# poi.net
KiCad netlist of a schematic drawn in EAGLE
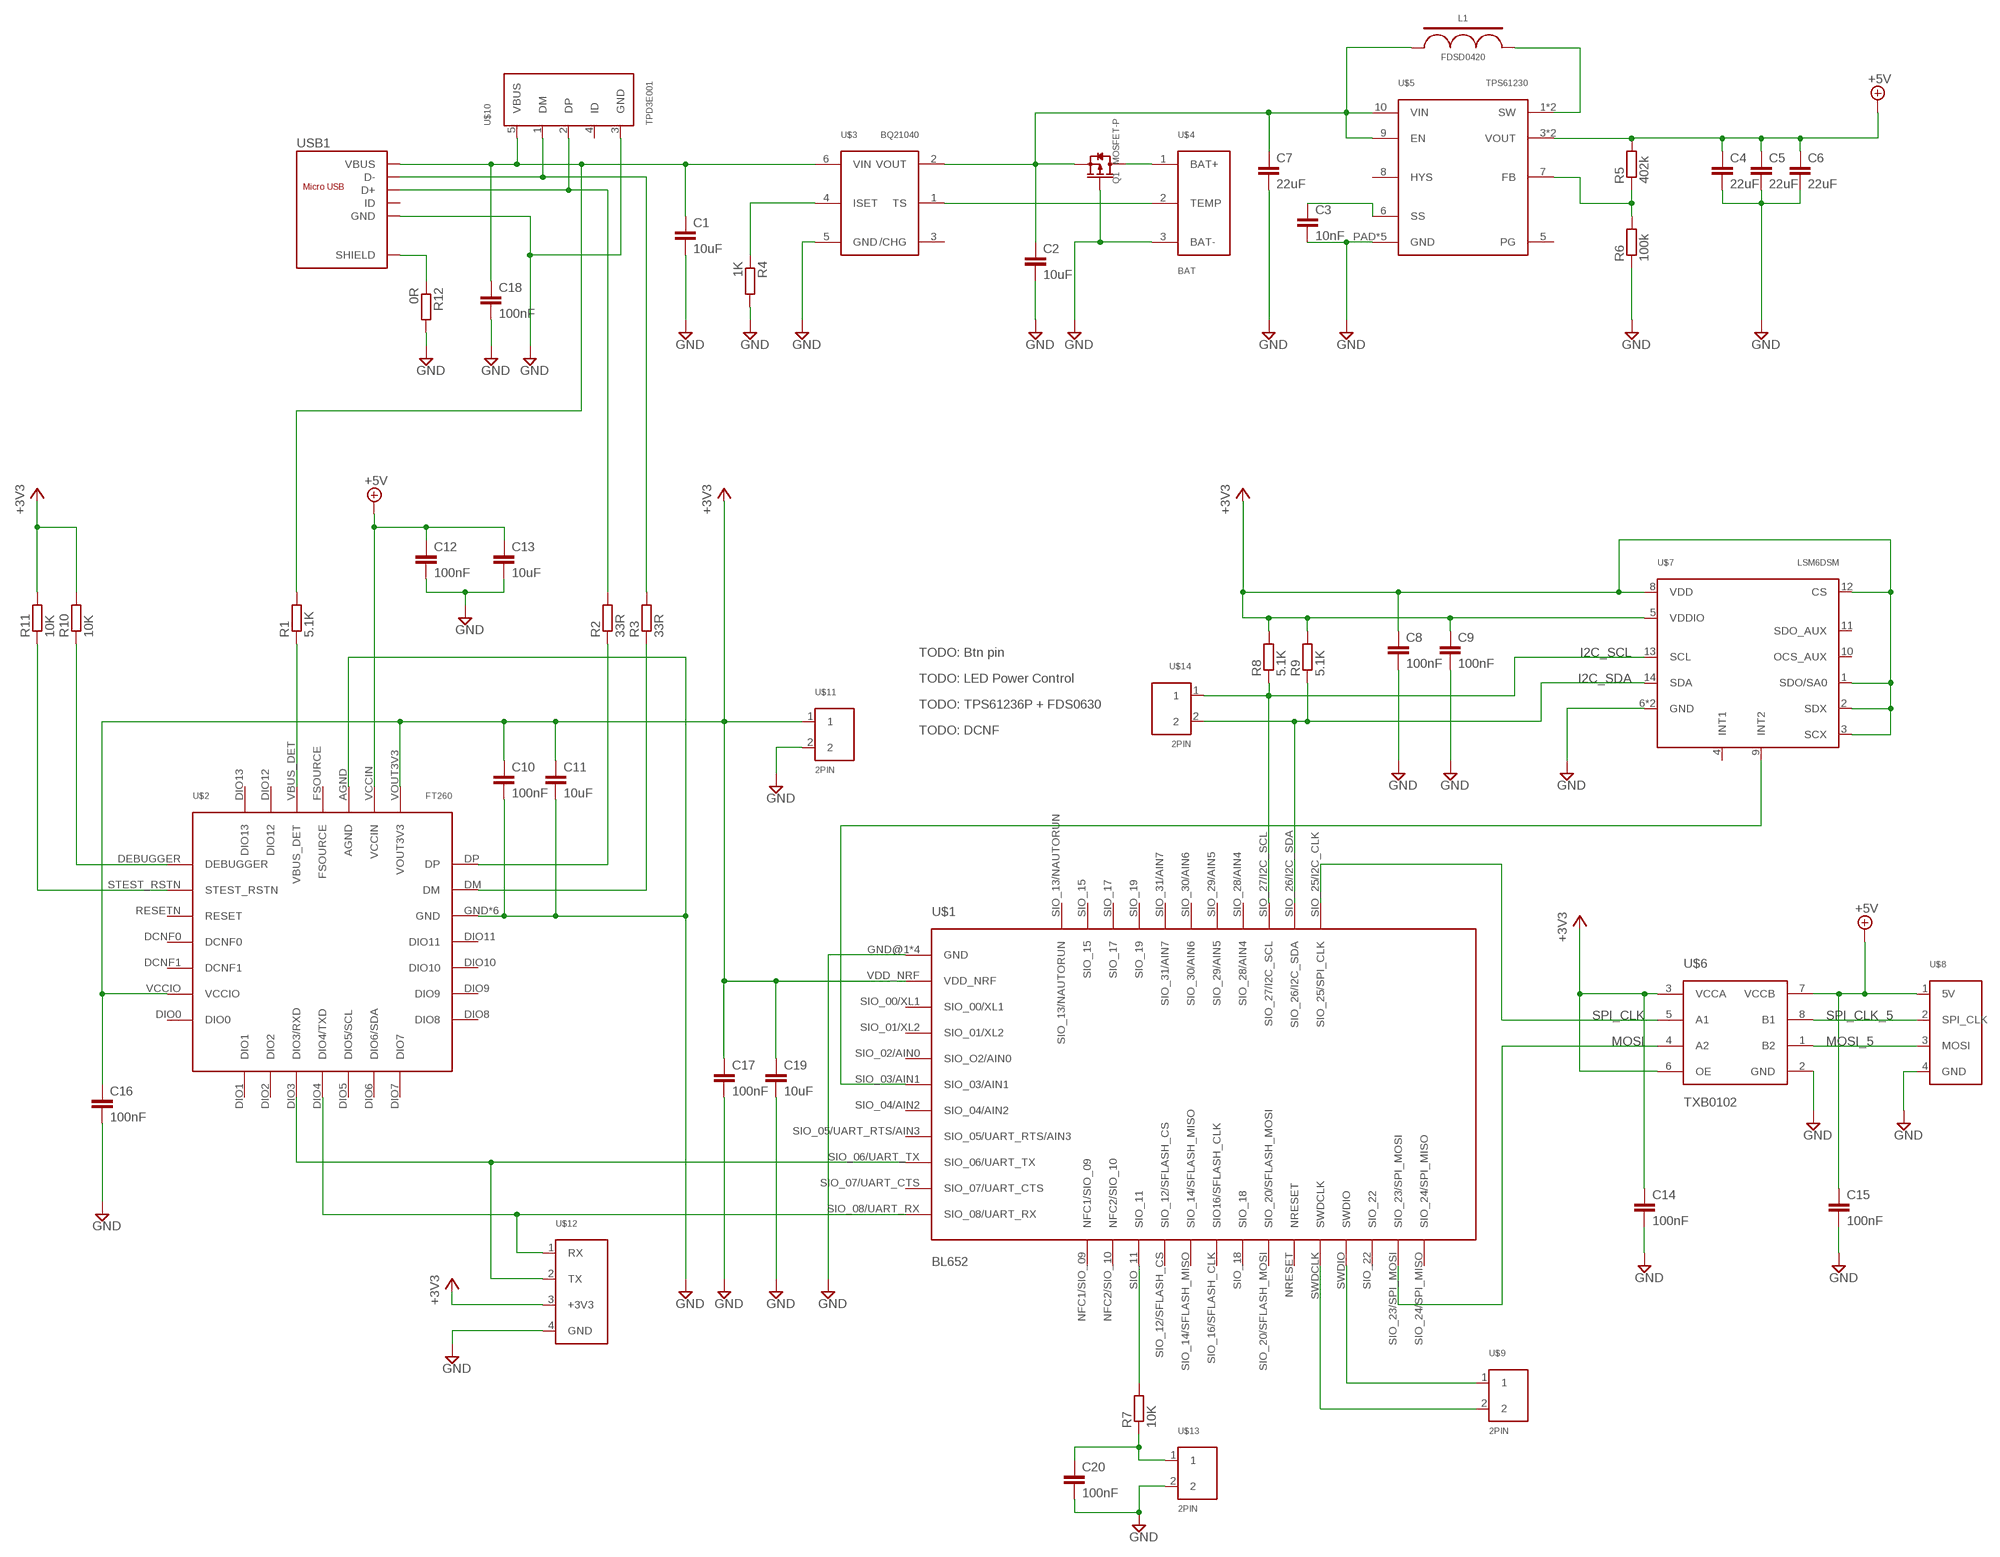
[diagram p0: schematic, sheet 1]

(export (version "E")
  (design (tool "Eeschema 10.0.6"))
  (components
    (comp (ref "C1")
      (value "10uF")
      (footprint "eagle-import:C0603")
      (libsource (lib "eagle-import") (part "C-EUC0603"))
    )
    (comp (ref "C2")
      (value "10uF")
      (footprint "eagle-import:C0603")
      (libsource (lib "eagle-import") (part "C-EUC0603"))
    )
    (comp (ref "C3")
      (value "10nF")
      (footprint "eagle-import:C0603")
      (libsource (lib "eagle-import") (part "C-EUC0603"))
    )
    (comp (ref "C4")
      (value "22uF")
      (footprint "eagle-import:C0603")
      (libsource (lib "eagle-import") (part "C-EUC0603"))
    )
    (comp (ref "C5")
      (value "22uF")
      (footprint "eagle-import:C0603")
      (libsource (lib "eagle-import") (part "C-EUC0603"))
    )
    (comp (ref "C6")
      (value "22uF")
      (footprint "eagle-import:C0603")
      (libsource (lib "eagle-import") (part "C-EUC0603"))
    )
    (comp (ref "C7")
      (value "22uF")
      (footprint "eagle-import:C0603")
      (libsource (lib "eagle-import") (part "C-EUC0603"))
    )
    (comp (ref "C8")
      (value "100nF")
      (footprint "eagle-import:C0603")
      (libsource (lib "eagle-import") (part "C-EUC0603"))
    )
    (comp (ref "C9")
      (value "100nF")
      (footprint "eagle-import:C0603")
      (libsource (lib "eagle-import") (part "C-EUC0603"))
    )
    (comp (ref "C10")
      (value "100nF")
      (footprint "eagle-import:C0603")
      (libsource (lib "eagle-import") (part "C-EUC0603"))
    )
    (comp (ref "C11")
      (value "10uF")
      (footprint "eagle-import:C0603")
      (libsource (lib "eagle-import") (part "C-EUC0603"))
    )
    (comp (ref "C12")
      (value "100nF")
      (footprint "eagle-import:C0603")
      (libsource (lib "eagle-import") (part "C-EUC0603"))
    )
    (comp (ref "C13")
      (value "10uF")
      (footprint "eagle-import:C0603")
      (libsource (lib "eagle-import") (part "C-EUC0603"))
    )
    (comp (ref "C14")
      (value "100nF")
      (footprint "eagle-import:C0603")
      (libsource (lib "eagle-import") (part "C-EUC0603"))
    )
    (comp (ref "C15")
      (value "100nF")
      (footprint "eagle-import:C0603")
      (libsource (lib "eagle-import") (part "C-EUC0603"))
    )
    (comp (ref "C16")
      (value "100nF")
      (footprint "eagle-import:C0603")
      (libsource (lib "eagle-import") (part "C-EUC0603"))
    )
    (comp (ref "C17")
      (value "100nF")
      (footprint "eagle-import:C0603")
      (libsource (lib "eagle-import") (part "C-EUC0603"))
    )
    (comp (ref "C18")
      (value "100nF")
      (footprint "eagle-import:C0603")
      (libsource (lib "eagle-import") (part "C-EUC0603"))
    )
    (comp (ref "C19")
      (value "10uF")
      (footprint "eagle-import:C0603")
      (libsource (lib "eagle-import") (part "C-EUC0603"))
    )
    (comp (ref "C20")
      (value "100nF")
      (footprint "eagle-import:C0603")
      (libsource (lib "eagle-import") (part "C-EUC0603"))
    )
    (comp (ref "L1")
      (value "FDSD0420")
      (footprint "eagle-import:FDSD0420")
      (libsource (lib "eagle-import") (part "FDSD0420"))
    )
    (comp (ref "Q1")
      (value "MOSFET-P")
      (footprint "eagle-import:SOT-23")
      (fields (field (name "MPN") "PMV65XPEA"))
      (libsource (lib "eagle-import") (part "MOSFET-P"))
    )
    (comp (ref "R1")
      (value "5.1K")
      (footprint "eagle-import:R0603")
      (libsource (lib "eagle-import") (part "R-EU_R0603"))
    )
    (comp (ref "R2")
      (value "33R")
      (footprint "eagle-import:R0603")
      (libsource (lib "eagle-import") (part "R-EU_R0603"))
    )
    (comp (ref "R3")
      (value "33R")
      (footprint "eagle-import:R0603")
      (libsource (lib "eagle-import") (part "R-EU_R0603"))
    )
    (comp (ref "R4")
      (value "1K")
      (footprint "eagle-import:R0603")
      (libsource (lib "eagle-import") (part "R-EU_R0603"))
    )
    (comp (ref "R5")
      (value "402k")
      (footprint "eagle-import:R0603")
      (libsource (lib "eagle-import") (part "R-EU_R0603"))
    )
    (comp (ref "R6")
      (value "100k")
      (footprint "eagle-import:R0603")
      (libsource (lib "eagle-import") (part "R-EU_R0603"))
    )
    (comp (ref "R7")
      (value "10K")
      (footprint "eagle-import:R0603")
      (libsource (lib "eagle-import") (part "R-EU_R0603"))
    )
    (comp (ref "R8")
      (value "5.1K")
      (footprint "eagle-import:R0603")
      (libsource (lib "eagle-import") (part "R-EU_R0603"))
    )
    (comp (ref "R9")
      (value "5.1K")
      (footprint "eagle-import:R0603")
      (libsource (lib "eagle-import") (part "R-EU_R0603"))
    )
    (comp (ref "R10")
      (value "10K")
      (footprint "eagle-import:R0603")
      (libsource (lib "eagle-import") (part "R-EU_R0603"))
    )
    (comp (ref "R11")
      (value "10K")
      (footprint "eagle-import:R0603")
      (libsource (lib "eagle-import") (part "R-EU_R0603"))
    )
    (comp (ref "R12")
      (value "0R")
      (footprint "eagle-import:R0603")
      (libsource (lib "eagle-import") (part "R-EU_R0603"))
    )
    (comp (ref "U$1")
      (value "BL652")
      (footprint "eagle-import:BL652")
      (fields (field (name "MF") "LAIRD") (field (name "MPN") "BL652-SA-01"))
      (libsource (lib "eagle-import") (part "BL652"))
    )
    (comp (ref "U$2")
      (value "FT260")
      (footprint "eagle-import:WQFN-28")
      (fields (field (name "MF") "FTDI") (field (name "MPN") "FT260Q-T"))
      (libsource (lib "eagle-import") (part "FT260"))
    )
    (comp (ref "U$3")
      (value "BQ21040")
      (footprint "eagle-import:SOT23-6")
      (fields (field (name "MF") "TEXAS INSTRUMENTS") (field (name "MPN") "BQ21040DBVT"))
      (libsource (lib "eagle-import") (part "BQ21040"))
    )
    (comp (ref "U$4")
      (value "BAT")
      (footprint "eagle-import:3PIN")
      (libsource (lib "eagle-import") (part "BAT"))
    )
    (comp (ref "U$5")
      (value "TPS61230")
      (footprint "eagle-import:VSON-10")
      (fields (field (name "MF") "TEXAS INSTRUMENTS") (field (name "MPN") " TPS61230DRCR TPS61230DRCR"))
      (libsource (lib "eagle-import") (part "TPS61230"))
    )
    (comp (ref "U$6")
      (value "TXB0102")
      (footprint "eagle-import:VSSOP-8")
      (fields (field (name "MF") "TEXAS INSTRUMENTS") (field (name "MPN") "TXB0102DCUR"))
      (libsource (lib "eagle-import") (part "TXB0102"))
    )
    (comp (ref "U$7")
      (value "LSM6DSM")
      (footprint "eagle-import:LGA-14L")
      (libsource (lib "eagle-import") (part "LSM6DSM"))
    )
    (comp (ref "U$8")
      (value "SPI-4PIN")
      (footprint "eagle-import:4PIN")
      (libsource (lib "eagle-import") (part "SPI-4PIN"))
    )
    (comp (ref "U$9")
      (value "2PIN")
      (footprint "eagle-import:2PIN")
      (libsource (lib "eagle-import") (part "2PIN"))
    )
    (comp (ref "U$10")
      (value "TPD3E001")
      (footprint "eagle-import:SOT-553")
      (libsource (lib "eagle-import") (part "TPD3E001"))
    )
    (comp (ref "U$11")
      (value "2PIN")
      (footprint "eagle-import:2PIN")
      (libsource (lib "eagle-import") (part "2PIN"))
    )
    (comp (ref "U$12")
      (value "UART-4PIN")
      (footprint "eagle-import:4PIN")
      (libsource (lib "eagle-import") (part "UART-4PIN"))
    )
    (comp (ref "U$13")
      (value "2PIN")
      (footprint "eagle-import:2PIN")
      (libsource (lib "eagle-import") (part "2PIN"))
    )
    (comp (ref "U$14")
      (value "2PIN")
      (footprint "eagle-import:2PIN")
      (libsource (lib "eagle-import") (part "2PIN"))
    )
    (comp (ref "USB1")
      (value "ZX62-B-5PA")
      (footprint "eagle-import:ZX62-B-5PA")
      (libsource (lib "eagle-import") (part "ZX62-B-5PA"))
    )
  )
  (nets
    (net (code "1") (name "+3V3") (class "Default")
      (node (ref "C10") (pin "1") (pinfunction "1_1") (pintype "passive"))
      (node (ref "C11") (pin "1") (pinfunction "1_1") (pintype "passive"))
      (node (ref "C14") (pin "1") (pinfunction "1_1") (pintype "passive"))
      (node (ref "C16") (pin "1") (pinfunction "1_1") (pintype "passive"))
      (node (ref "C17") (pin "1") (pinfunction "1_1") (pintype "passive"))
      (node (ref "C19") (pin "1") (pinfunction "1_1") (pintype "passive"))
      (node (ref "C8") (pin "1") (pinfunction "1_1") (pintype "passive"))
      (node (ref "C9") (pin "1") (pinfunction "1_1") (pintype "passive"))
      (node (ref "R10") (pin "2") (pinfunction "2_2") (pintype "passive"))
      (node (ref "R11") (pin "2") (pinfunction "2_2") (pintype "passive"))
      (node (ref "R8") (pin "2") (pinfunction "2_2") (pintype "passive"))
      (node (ref "R9") (pin "2") (pinfunction "2_2") (pintype "passive"))
      (node (ref "U$1") (pin "VDD_NRF") (pinfunction "VDD_NRF_VDD_NRF") (pintype "power_in"))
      (node (ref "U$11") (pin "1") (pinfunction "1_1") (pintype "bidirectional"))
      (node (ref "U$12") (pin "3") (pinfunction "+3V3_3") (pintype "power_in"))
      (node (ref "U$2") (pin "VCCIO") (pinfunction "VCCIO_VCCIO") (pintype "bidirectional"))
      (node (ref "U$2") (pin "VOUT3V3") (pinfunction "VOUT3V3_VOUT3V3") (pintype "bidirectional"))
      (node (ref "U$6") (pin "3") (pinfunction "VCCA_3") (pintype "power_in"))
      (node (ref "U$6") (pin "6") (pinfunction "OE_6") (pintype "input"))
      (node (ref "U$7") (pin "1") (pinfunction "SDO/SA0_1") (pintype "bidirectional"))
      (node (ref "U$7") (pin "12") (pinfunction "CS_12") (pintype "bidirectional"))
      (node (ref "U$7") (pin "2") (pinfunction "SDX_2") (pintype "bidirectional"))
      (node (ref "U$7") (pin "3") (pinfunction "SCX_3") (pintype "bidirectional"))
      (node (ref "U$7") (pin "5") (pinfunction "VDDIO_5") (pintype "bidirectional"))
      (node (ref "U$7") (pin "8") (pinfunction "VDD_8") (pintype "bidirectional"))
    )
    (net (code "2") (name "+5V") (class "Default")
      (node (ref "C12") (pin "1") (pinfunction "1_1") (pintype "passive"))
      (node (ref "C13") (pin "1") (pinfunction "1_1") (pintype "passive"))
      (node (ref "C15") (pin "1") (pinfunction "1_1") (pintype "passive"))
      (node (ref "C4") (pin "1") (pinfunction "1_1") (pintype "passive"))
      (node (ref "C5") (pin "1") (pinfunction "1_1") (pintype "passive"))
      (node (ref "C6") (pin "1") (pinfunction "1_1") (pintype "passive"))
      (node (ref "R5") (pin "2") (pinfunction "2_2") (pintype "passive"))
      (node (ref "U$2") (pin "VCCIN") (pinfunction "VCCIN_VCCIN") (pintype "bidirectional"))
      (node (ref "U$5") (pin "3") (pinfunction "VOUT_3") (pintype "power_in"))
      (node (ref "U$5") (pin "4") (pinfunction "VOUT_4") (pintype "power_in"))
      (node (ref "U$6") (pin "7") (pinfunction "VCCB_7") (pintype "power_in"))
      (node (ref "U$8") (pin "1") (pinfunction "5V_1") (pintype "power_in"))
    )
    (net (code "3") (name "/I2C_SCL") (class "Default")
      (node (ref "R8") (pin "1") (pinfunction "1_1") (pintype "passive"))
      (node (ref "U$1") (pin "SIO_27/I2C_SCL") (pinfunction "SIO_27/I2C_SCL_SIO_27/I2C_SCL") (pintype "bidirectional"))
      (node (ref "U$14") (pin "1") (pinfunction "1_1") (pintype "bidirectional"))
      (node (ref "U$7") (pin "13") (pinfunction "SCL_13") (pintype "bidirectional"))
    )
    (net (code "4") (name "/I2C_SDA") (class "Default")
      (node (ref "R9") (pin "1") (pinfunction "1_1") (pintype "passive"))
      (node (ref "U$1") (pin "SIO_26/I2C_SDA") (pinfunction "SIO_26/I2C_SDA_SIO_26/I2C_SDA") (pintype "bidirectional"))
      (node (ref "U$14") (pin "2") (pinfunction "2_2") (pintype "bidirectional"))
      (node (ref "U$7") (pin "14") (pinfunction "SDA_14") (pintype "bidirectional"))
    )
    (net (code "5") (name "/MOSI") (class "Default")
      (node (ref "U$1") (pin "SIO_23/SPI_MOSI") (pinfunction "SIO_23/SPI_MOSI_SIO_23/SPI_MOSI") (pintype "bidirectional"))
      (node (ref "U$6") (pin "4") (pinfunction "A2_4") (pintype "bidirectional"))
    )
    (net (code "6") (name "/MOSI_5") (class "Default")
      (node (ref "U$6") (pin "1") (pinfunction "B2_1") (pintype "bidirectional"))
      (node (ref "U$8") (pin "3") (pinfunction "MOSI_3") (pintype "output"))
    )
    (net (code "7") (name "/SPI_CLK") (class "Default")
      (node (ref "U$1") (pin "SIO_25/I2C_CLK") (pinfunction "SIO_25/SPI_CLK_SIO_25/I2C_CLK") (pintype "bidirectional"))
      (node (ref "U$6") (pin "5") (pinfunction "A1_5") (pintype "bidirectional"))
    )
    (net (code "8") (name "/SPI_CLK_5") (class "Default")
      (node (ref "U$6") (pin "8") (pinfunction "B1_8") (pintype "bidirectional"))
      (node (ref "U$8") (pin "2") (pinfunction "SPI_CLK_2") (pintype "input"))
    )
    (net (code "9") (name "GND") (class "Default")
      (node (ref "C1") (pin "2") (pinfunction "2_2") (pintype "passive"))
      (node (ref "C10") (pin "2") (pinfunction "2_2") (pintype "passive"))
      (node (ref "C11") (pin "2") (pinfunction "2_2") (pintype "passive"))
      (node (ref "C12") (pin "2") (pinfunction "2_2") (pintype "passive"))
      (node (ref "C13") (pin "2") (pinfunction "2_2") (pintype "passive"))
      (node (ref "C14") (pin "2") (pinfunction "2_2") (pintype "passive"))
      (node (ref "C15") (pin "2") (pinfunction "2_2") (pintype "passive"))
      (node (ref "C16") (pin "2") (pinfunction "2_2") (pintype "passive"))
      (node (ref "C17") (pin "2") (pinfunction "2_2") (pintype "passive"))
      (node (ref "C18") (pin "2") (pinfunction "2_2") (pintype "passive"))
      (node (ref "C19") (pin "2") (pinfunction "2_2") (pintype "passive"))
      (node (ref "C2") (pin "2") (pinfunction "2_2") (pintype "passive"))
      (node (ref "C20") (pin "2") (pinfunction "2_2") (pintype "passive"))
      (node (ref "C3") (pin "2") (pinfunction "2_2") (pintype "passive"))
      (node (ref "C4") (pin "2") (pinfunction "2_2") (pintype "passive"))
      (node (ref "C5") (pin "2") (pinfunction "2_2") (pintype "passive"))
      (node (ref "C6") (pin "2") (pinfunction "2_2") (pintype "passive"))
      (node (ref "C7") (pin "2") (pinfunction "2_2") (pintype "passive"))
      (node (ref "C8") (pin "2") (pinfunction "2_2") (pintype "passive"))
      (node (ref "C9") (pin "2") (pinfunction "2_2") (pintype "passive"))
      (node (ref "Q1") (pin "1") (pinfunction "G_1") (pintype "passive"))
      (node (ref "R12") (pin "2") (pinfunction "2_2") (pintype "passive"))
      (node (ref "R4") (pin "2") (pinfunction "2_2") (pintype "passive"))
      (node (ref "R6") (pin "1") (pinfunction "1_1") (pintype "passive"))
      (node (ref "U$1") (pin "GND@1") (pinfunction "GND_GND@1") (pintype "power_in"))
      (node (ref "U$1") (pin "GND@2") (pinfunction "GND_GND@2") (pintype "power_in"))
      (node (ref "U$1") (pin "GND@3") (pinfunction "GND_GND@3") (pintype "power_in"))
      (node (ref "U$1") (pin "GND@4") (pinfunction "GND_GND@4") (pintype "power_in"))
      (node (ref "U$10") (pin "3") (pinfunction "GND_3") (pintype "bidirectional"))
      (node (ref "U$11") (pin "2") (pinfunction "2_2") (pintype "bidirectional"))
      (node (ref "U$12") (pin "4") (pinfunction "GND_4") (pintype "power_in"))
      (node (ref "U$13") (pin "2") (pinfunction "2_2") (pintype "bidirectional"))
      (node (ref "U$2") (pin "AGND") (pinfunction "AGND_AGND") (pintype "bidirectional"))
      (node (ref "U$2") (pin "GND") (pinfunction "GND_GND") (pintype "bidirectional"))
      (node (ref "U$2") (pin "PAD") (pinfunction "GND_PAD") (pintype "bidirectional"))
      (node (ref "U$2") (pin "V1") (pinfunction "GND_V1") (pintype "bidirectional"))
      (node (ref "U$2") (pin "V2") (pinfunction "GND_V2") (pintype "bidirectional"))
      (node (ref "U$2") (pin "V3") (pinfunction "GND_V3") (pintype "bidirectional"))
      (node (ref "U$2") (pin "V4") (pinfunction "GND_V4") (pintype "bidirectional"))
      (node (ref "U$3") (pin "5") (pinfunction "GND_5") (pintype "power_in"))
      (node (ref "U$4") (pin "3") (pinfunction "BAT-_3") (pintype "power_in"))
      (node (ref "U$5") (pin "PAD") (pinfunction "GND_PAD") (pintype "power_in"))
      (node (ref "U$5") (pin "V1") (pinfunction "GND_V1") (pintype "power_in"))
      (node (ref "U$5") (pin "V2") (pinfunction "GND_V2") (pintype "power_in"))
      (node (ref "U$5") (pin "V3") (pinfunction "GND_V3") (pintype "power_in"))
      (node (ref "U$5") (pin "V4") (pinfunction "GND_V4") (pintype "power_in"))
      (node (ref "U$6") (pin "2") (pinfunction "GND_2") (pintype "power_in"))
      (node (ref "U$7") (pin "6") (pinfunction "GND_6") (pintype "bidirectional"))
      (node (ref "U$7") (pin "7") (pinfunction "GND_7") (pintype "bidirectional"))
      (node (ref "U$8") (pin "4") (pinfunction "GND_4") (pintype "power_in"))
      (node (ref "USB1") (pin "5") (pinfunction "GND_5") (pintype "power_in"))
    )
    (net (code "10") (name "Net-(C20-Pad1)") (class "Default")
      (node (ref "C20") (pin "1") (pinfunction "1_1") (pintype "passive"))
      (node (ref "R7") (pin "1") (pinfunction "1_1") (pintype "passive"))
      (node (ref "U$13") (pin "1") (pinfunction "1_1") (pintype "bidirectional"))
    )
    (net (code "11") (name "Net-(L1-Pad2)") (class "Default")
      (node (ref "L1") (pin "2") (pinfunction "2_2") (pintype "passive"))
      (node (ref "U$5") (pin "1") (pinfunction "SW_1") (pintype "power_in"))
      (node (ref "U$5") (pin "2") (pinfunction "SW_2") (pintype "power_in"))
    )
    (net (code "12") (name "Net-(Q1-D)") (class "Default")
      (node (ref "Q1") (pin "3") (pinfunction "D_3") (pintype "passive"))
      (node (ref "U$4") (pin "1") (pinfunction "BAT+_1") (pintype "power_in"))
    )
    (net (code "13") (name "Net-(Q1-S)") (class "Default")
      (node (ref "C2") (pin "1") (pinfunction "1_1") (pintype "passive"))
      (node (ref "C7") (pin "1") (pinfunction "1_1") (pintype "passive"))
      (node (ref "L1") (pin "1") (pinfunction "1_1") (pintype "passive"))
      (node (ref "Q1") (pin "2") (pinfunction "S_2") (pintype "passive"))
      (node (ref "U$3") (pin "2") (pinfunction "VOUT_2") (pintype "power_in"))
      (node (ref "U$5") (pin "10") (pinfunction "VIN_10") (pintype "power_in"))
      (node (ref "U$5") (pin "9") (pinfunction "EN_9") (pintype "input"))
    )
    (net (code "14") (name "Net-(R1-Pad1)") (class "Default")
      (node (ref "R1") (pin "1") (pinfunction "1_1") (pintype "passive"))
      (node (ref "U$2") (pin "VBUS_DET") (pinfunction "VBUS_DET_VBUS_DET") (pintype "bidirectional"))
    )
    (net (code "15") (name "Net-(R2-Pad1)") (class "Default")
      (node (ref "R2") (pin "1") (pinfunction "1_1") (pintype "passive"))
      (node (ref "U$2") (pin "DP") (pinfunction "DP_DP") (pintype "bidirectional"))
    )
    (net (code "16") (name "Net-(R3-Pad1)") (class "Default")
      (node (ref "R3") (pin "1") (pinfunction "1_1") (pintype "passive"))
      (node (ref "U$2") (pin "DM") (pinfunction "DM_DM") (pintype "bidirectional"))
    )
    (net (code "17") (name "Net-(R7-Pad2)") (class "Default")
      (node (ref "R7") (pin "2") (pinfunction "2_2") (pintype "passive"))
      (node (ref "U$1") (pin "SIO_11") (pinfunction "SIO_11_SIO_11") (pintype "bidirectional"))
    )
    (net (code "18") (name "Net-(R10-Pad1)") (class "Default")
      (node (ref "R10") (pin "1") (pinfunction "1_1") (pintype "passive"))
      (node (ref "U$2") (pin "DEBUGGER") (pinfunction "DEBUGGER_DEBUGGER") (pintype "bidirectional"))
    )
    (net (code "19") (name "Net-(R11-Pad1)") (class "Default")
      (node (ref "R11") (pin "1") (pinfunction "1_1") (pintype "passive"))
      (node (ref "U$2") (pin "STEST_RSTN") (pinfunction "STEST_RSTN_STEST_RSTN") (pintype "bidirectional"))
    )
    (net (code "20") (name "Net-(R12-Pad1)") (class "Default")
      (node (ref "R12") (pin "1") (pinfunction "1_1") (pintype "passive"))
      (node (ref "USB1") (pin "P1") (pinfunction "SHIELD_P1") (pintype "power_in"))
      (node (ref "USB1") (pin "P2") (pinfunction "SHIELD_P2") (pintype "power_in"))
      (node (ref "USB1") (pin "P3") (pinfunction "SHIELD_P3") (pintype "power_in"))
      (node (ref "USB1") (pin "P4") (pinfunction "SHIELD_P4") (pintype "power_in"))
      (node (ref "USB1") (pin "P5") (pinfunction "SHIELD_P5") (pintype "power_in"))
      (node (ref "USB1") (pin "P6") (pinfunction "SHIELD_P6") (pintype "power_in"))
    )
    (net (code "21") (name "Net-(U$1-PadSWDCLK)") (class "Default")
      (node (ref "U$1") (pin "SWDCLK") (pinfunction "SWDCLK_SWDCLK") (pintype "bidirectional"))
      (node (ref "U$9") (pin "2") (pinfunction "2_2") (pintype "bidirectional"))
    )
    (net (code "22") (name "Net-(U$1-PadSWDIO)") (class "Default")
      (node (ref "U$1") (pin "SWDIO") (pinfunction "SWDIO_SWDIO") (pintype "bidirectional"))
      (node (ref "U$9") (pin "1") (pinfunction "1_1") (pintype "bidirectional"))
    )
    (net (code "23") (name "Net-(U$3-ISET)") (class "Default")
      (node (ref "R4") (pin "1") (pinfunction "1_1") (pintype "passive"))
      (node (ref "U$3") (pin "4") (pinfunction "ISET_4") (pintype "input"))
    )
    (net (code "24") (name "Net-(U$3-TS)") (class "Default")
      (node (ref "U$3") (pin "1") (pinfunction "TS_1") (pintype "input"))
      (node (ref "U$4") (pin "2") (pinfunction "TEMP_2") (pintype "output"))
    )
    (net (code "25") (name "Net-(U$5-FB)") (class "Default")
      (node (ref "R5") (pin "1") (pinfunction "1_1") (pintype "passive"))
      (node (ref "R6") (pin "2") (pinfunction "2_2") (pintype "passive"))
      (node (ref "U$5") (pin "7") (pinfunction "FB_7") (pintype "input"))
    )
    (net (code "26") (name "Net-(U$5-SS)") (class "Default")
      (node (ref "C3") (pin "1") (pinfunction "1_1") (pintype "passive"))
      (node (ref "U$5") (pin "6") (pinfunction "SS_6") (pintype "input"))
    )
    (net (code "27") (name "Net-(U$7-INT2)") (class "Default")
      (node (ref "U$1") (pin "SIO_03/AIN1") (pinfunction "SIO_03/AIN1_SIO_03/AIN1") (pintype "bidirectional"))
      (node (ref "U$7") (pin "9") (pinfunction "INT2_9") (pintype "bidirectional"))
    )
    (net (code "28") (name "Net-(U$10-DM)") (class "Default")
      (node (ref "R3") (pin "2") (pinfunction "2_2") (pintype "passive"))
      (node (ref "U$10") (pin "1") (pinfunction "DM_1") (pintype "bidirectional"))
      (node (ref "USB1") (pin "2") (pinfunction "D-_2") (pintype "bidirectional"))
    )
    (net (code "29") (name "Net-(U$10-DP)") (class "Default")
      (node (ref "R2") (pin "2") (pinfunction "2_2") (pintype "passive"))
      (node (ref "U$10") (pin "2") (pinfunction "DP_2") (pintype "bidirectional"))
      (node (ref "USB1") (pin "3") (pinfunction "D+_3") (pintype "bidirectional"))
    )
    (net (code "30") (name "Net-(U$10-VBUS)") (class "Default")
      (node (ref "C1") (pin "1") (pinfunction "1_1") (pintype "passive"))
      (node (ref "C18") (pin "1") (pinfunction "1_1") (pintype "passive"))
      (node (ref "R1") (pin "2") (pinfunction "2_2") (pintype "passive"))
      (node (ref "U$10") (pin "5") (pinfunction "VBUS_5") (pintype "bidirectional"))
      (node (ref "U$3") (pin "6") (pinfunction "VIN_6") (pintype "power_in"))
      (node (ref "USB1") (pin "1") (pinfunction "VBUS_1") (pintype "power_in"))
    )
    (net (code "31") (name "Net-(U$12-RX)") (class "Default")
      (node (ref "U$1") (pin "SIO_08/UART_RX") (pinfunction "SIO_08/UART_RX_SIO_08/UART_RX") (pintype "bidirectional"))
      (node (ref "U$12") (pin "1") (pinfunction "RX_1") (pintype "bidirectional"))
      (node (ref "U$2") (pin "DIO4") (pinfunction "DIO4/TXD_DIO4") (pintype "bidirectional"))
    )
    (net (code "32") (name "Net-(U$12-TX)") (class "Default")
      (node (ref "U$1") (pin "SIO_06/UART_TX") (pinfunction "SIO_06/UART_TX_SIO_06/UART_TX") (pintype "bidirectional"))
      (node (ref "U$12") (pin "2") (pinfunction "TX_2") (pintype "bidirectional"))
      (node (ref "U$2") (pin "DIO3") (pinfunction "DIO3/RXD_DIO3") (pintype "bidirectional"))
    )
    (net (code "33") (name "unconnected-(U$1-PadNFC1{slash}SIO_09)") (class "Default")
      (node (ref "U$1") (pin "NFC1/SIO_09") (pinfunction "NFC1/SIO_09_NFC1/SIO_09") (pintype "bidirectional"))
    )
    (net (code "34") (name "unconnected-(U$1-PadNFC2{slash}SIO_10)") (class "Default")
      (node (ref "U$1") (pin "NFC2/SIO_10") (pinfunction "NFC2/SIO_10_NFC2/SIO_10") (pintype "bidirectional"))
    )
    (net (code "35") (name "unconnected-(U$1-PadNRESET)") (class "Default")
      (node (ref "U$1") (pin "NRESET") (pinfunction "NRESET_NRESET") (pintype "bidirectional"))
    )
    (net (code "36") (name "unconnected-(U$1-PadSIO_00{slash}XL1)") (class "Default")
      (node (ref "U$1") (pin "SIO_00/XL1") (pinfunction "SIO_00/XL1_SIO_00/XL1") (pintype "bidirectional"))
    )
    (net (code "37") (name "unconnected-(U$1-PadSIO_01{slash}XL2)") (class "Default")
      (node (ref "U$1") (pin "SIO_01/XL2") (pinfunction "SIO_01/XL2_SIO_01/XL2") (pintype "bidirectional"))
    )
    (net (code "38") (name "unconnected-(U$1-PadSIO_04{slash}AIN2)") (class "Default")
      (node (ref "U$1") (pin "SIO_04/AIN2") (pinfunction "SIO_04/AIN2_SIO_04/AIN2") (pintype "bidirectional"))
    )
    (net (code "39") (name "unconnected-(U$1-PadSIO_05{slash}UART_RTS{slash}AIN3)") (class "Default")
      (node (ref "U$1") (pin "SIO_05/UART_RTS/AIN3") (pinfunction "SIO_05/UART_RTS/AIN3_SIO_05/UART_RTS/AIN3") (pintype "bidirectional"))
    )
    (net (code "40") (name "unconnected-(U$1-PadSIO_07{slash}UART_CTS)") (class "Default")
      (node (ref "U$1") (pin "SIO_07/UART_CTS") (pinfunction "SIO_07/UART_CTS_SIO_07/UART_CTS") (pintype "bidirectional"))
    )
    (net (code "41") (name "unconnected-(U$1-PadSIO_12{slash}SFLASH_CS)") (class "Default")
      (node (ref "U$1") (pin "SIO_12/SFLASH_CS") (pinfunction "SIO_12/SFLASH_CS_SIO_12/SFLASH_CS") (pintype "bidirectional"))
    )
    (net (code "42") (name "unconnected-(U$1-PadSIO_13{slash}NAUTORUN)") (class "Default")
      (node (ref "U$1") (pin "SIO_13/NAUTORUN") (pinfunction "SIO_13/NAUTORUN_SIO_13/NAUTORUN") (pintype "bidirectional"))
    )
    (net (code "43") (name "unconnected-(U$1-PadSIO_14{slash}SFLASH_MISO)") (class "Default")
      (node (ref "U$1") (pin "SIO_14/SFLASH_MISO") (pinfunction "SIO_14/SFLASH_MISO_SIO_14/SFLASH_MISO") (pintype "bidirectional"))
    )
    (net (code "44") (name "unconnected-(U$1-PadSIO_15)") (class "Default")
      (node (ref "U$1") (pin "SIO_15") (pinfunction "SIO_15_SIO_15") (pintype "bidirectional"))
    )
    (net (code "45") (name "unconnected-(U$1-PadSIO_17)") (class "Default")
      (node (ref "U$1") (pin "SIO_17") (pinfunction "SIO_17_SIO_17") (pintype "bidirectional"))
    )
    (net (code "46") (name "unconnected-(U$1-PadSIO_18)") (class "Default")
      (node (ref "U$1") (pin "SIO_18") (pinfunction "SIO_18_SIO_18") (pintype "bidirectional"))
    )
    (net (code "47") (name "unconnected-(U$1-PadSIO_19)") (class "Default")
      (node (ref "U$1") (pin "SIO_19") (pinfunction "SIO_19_SIO_19") (pintype "bidirectional"))
    )
    (net (code "48") (name "unconnected-(U$1-PadSIO_20{slash}SFLASH_MOSI)") (class "Default")
      (node (ref "U$1") (pin "SIO_20/SFLASH_MOSI") (pinfunction "SIO_20/SFLASH_MOSI_SIO_20/SFLASH_MOSI") (pintype "bidirectional"))
    )
    (net (code "49") (name "unconnected-(U$1-PadSIO_22)") (class "Default")
      (node (ref "U$1") (pin "SIO_22") (pinfunction "SIO_22_SIO_22") (pintype "bidirectional"))
    )
    (net (code "50") (name "unconnected-(U$1-PadSIO_24{slash}SPI_MISO)") (class "Default")
      (node (ref "U$1") (pin "SIO_24/SPI_MISO") (pinfunction "SIO_24/SPI_MISO_SIO_24/SPI_MISO") (pintype "bidirectional"))
    )
    (net (code "51") (name "unconnected-(U$1-PadSIO_28{slash}AIN4)") (class "Default")
      (node (ref "U$1") (pin "SIO_28/AIN4") (pinfunction "SIO_28/AIN4_SIO_28/AIN4") (pintype "bidirectional"))
    )
    (net (code "52") (name "unconnected-(U$1-PadSIO_29{slash}AIN5)") (class "Default")
      (node (ref "U$1") (pin "SIO_29/AIN5") (pinfunction "SIO_29/AIN5_SIO_29/AIN5") (pintype "bidirectional"))
    )
    (net (code "53") (name "unconnected-(U$1-PadSIO_30{slash}AIN6)") (class "Default")
      (node (ref "U$1") (pin "SIO_30/AIN6") (pinfunction "SIO_30/AIN6_SIO_30/AIN6") (pintype "bidirectional"))
    )
    (net (code "54") (name "unconnected-(U$1-PadSIO_31{slash}AIN7)") (class "Default")
      (node (ref "U$1") (pin "SIO_31/AIN7") (pinfunction "SIO_31/AIN7_SIO_31/AIN7") (pintype "bidirectional"))
    )
    (net (code "55") (name "unconnected-(U$1-SIO16{slash}SFLASH_CLK-PadSIO_16{slash}SFLASH_CLK)") (class "Default")
      (node (ref "U$1") (pin "SIO_16/SFLASH_CLK") (pinfunction "SIO16/SFLASH_CLK_SIO_16/SFLASH_CLK") (pintype "bidirectional"))
    )
    (net (code "56") (name "unconnected-(U$1-SIO_O2{slash}AIN0-PadSIO_02{slash}AIN0)") (class "Default")
      (node (ref "U$1") (pin "SIO_02/AIN0") (pinfunction "SIO_O2/AIN0_SIO_02/AIN0") (pintype "bidirectional"))
    )
    (net (code "57") (name "unconnected-(U$2-DIO5{slash}SCL-PadDIO5)") (class "Default")
      (node (ref "U$2") (pin "DIO5") (pinfunction "DIO5/SCL_DIO5") (pintype "bidirectional"))
    )
    (net (code "58") (name "unconnected-(U$2-DIO6{slash}SDA-PadDIO6)") (class "Default")
      (node (ref "U$2") (pin "DIO6") (pinfunction "DIO6/SDA_DIO6") (pintype "bidirectional"))
    )
    (net (code "59") (name "unconnected-(U$2-PadDCNF0)") (class "Default")
      (node (ref "U$2") (pin "DCNF0") (pinfunction "DCNF0_DCNF0") (pintype "bidirectional"))
    )
    (net (code "60") (name "unconnected-(U$2-PadDCNF1)") (class "Default")
      (node (ref "U$2") (pin "DCNF1") (pinfunction "DCNF1_DCNF1") (pintype "bidirectional"))
    )
    (net (code "61") (name "unconnected-(U$2-PadDIO0)") (class "Default")
      (node (ref "U$2") (pin "DIO0") (pinfunction "DIO0_DIO0") (pintype "bidirectional"))
    )
    (net (code "62") (name "unconnected-(U$2-PadDIO1)") (class "Default")
      (node (ref "U$2") (pin "DIO1") (pinfunction "DIO1_DIO1") (pintype "bidirectional"))
    )
    (net (code "63") (name "unconnected-(U$2-PadDIO2)") (class "Default")
      (node (ref "U$2") (pin "DIO2") (pinfunction "DIO2_DIO2") (pintype "bidirectional"))
    )
    (net (code "64") (name "unconnected-(U$2-PadDIO7)") (class "Default")
      (node (ref "U$2") (pin "DIO7") (pinfunction "DIO7_DIO7") (pintype "bidirectional"))
    )
    (net (code "65") (name "unconnected-(U$2-PadDIO8)") (class "Default")
      (node (ref "U$2") (pin "DIO8") (pinfunction "DIO8_DIO8") (pintype "bidirectional"))
    )
    (net (code "66") (name "unconnected-(U$2-PadDIO9)") (class "Default")
      (node (ref "U$2") (pin "DIO9") (pinfunction "DIO9_DIO9") (pintype "bidirectional"))
    )
    (net (code "67") (name "unconnected-(U$2-PadDIO10)") (class "Default")
      (node (ref "U$2") (pin "DIO10") (pinfunction "DIO10_DIO10") (pintype "bidirectional"))
    )
    (net (code "68") (name "unconnected-(U$2-PadDIO11)") (class "Default")
      (node (ref "U$2") (pin "DIO11") (pinfunction "DIO11_DIO11") (pintype "bidirectional"))
    )
    (net (code "69") (name "unconnected-(U$2-PadDIO12)") (class "Default")
      (node (ref "U$2") (pin "DIO12") (pinfunction "DIO12_DIO12") (pintype "bidirectional"))
    )
    (net (code "70") (name "unconnected-(U$2-PadDIO13)") (class "Default")
      (node (ref "U$2") (pin "DIO13") (pinfunction "DIO13_DIO13") (pintype "bidirectional"))
    )
    (net (code "71") (name "unconnected-(U$2-PadFSOURCE)") (class "Default")
      (node (ref "U$2") (pin "FSOURCE") (pinfunction "FSOURCE_FSOURCE") (pintype "bidirectional"))
    )
    (net (code "72") (name "unconnected-(U$2-RESET-PadRESETN)") (class "Default")
      (node (ref "U$2") (pin "RESETN") (pinfunction "RESET_RESETN") (pintype "bidirectional"))
    )
    (net (code "73") (name "unconnected-(U$3-{slash}CHG-Pad3)") (class "Default")
      (node (ref "U$3") (pin "3") (pinfunction "/CHG_3") (pintype "output"))
    )
    (net (code "74") (name "unconnected-(U$5-HYS-Pad8)") (class "Default")
      (node (ref "U$5") (pin "8") (pinfunction "HYS_8") (pintype "output"))
    )
    (net (code "75") (name "unconnected-(U$5-PG-Pad5)") (class "Default")
      (node (ref "U$5") (pin "5") (pinfunction "PG_5") (pintype "output"))
    )
    (net (code "76") (name "unconnected-(U$7-INT1-Pad4)") (class "Default")
      (node (ref "U$7") (pin "4") (pinfunction "INT1_4") (pintype "bidirectional"))
    )
    (net (code "77") (name "unconnected-(U$7-OCS_AUX-Pad10)") (class "Default")
      (node (ref "U$7") (pin "10") (pinfunction "OCS_AUX_10") (pintype "bidirectional"))
    )
    (net (code "78") (name "unconnected-(U$7-SDO_AUX-Pad11)") (class "Default")
      (node (ref "U$7") (pin "11") (pinfunction "SDO_AUX_11") (pintype "bidirectional"))
    )
    (net (code "79") (name "unconnected-(U$10-ID-Pad4)") (class "Default")
      (node (ref "U$10") (pin "4") (pinfunction "ID_4") (pintype "bidirectional"))
    )
    (net (code "80") (name "unconnected-(USB1-ID-Pad4)") (class "Default")
      (node (ref "USB1") (pin "4") (pinfunction "ID_4") (pintype "bidirectional"))
    )
  )
)
